# Power_Supply.net
KiCad netlist of a schematic drawn in Altium Designer
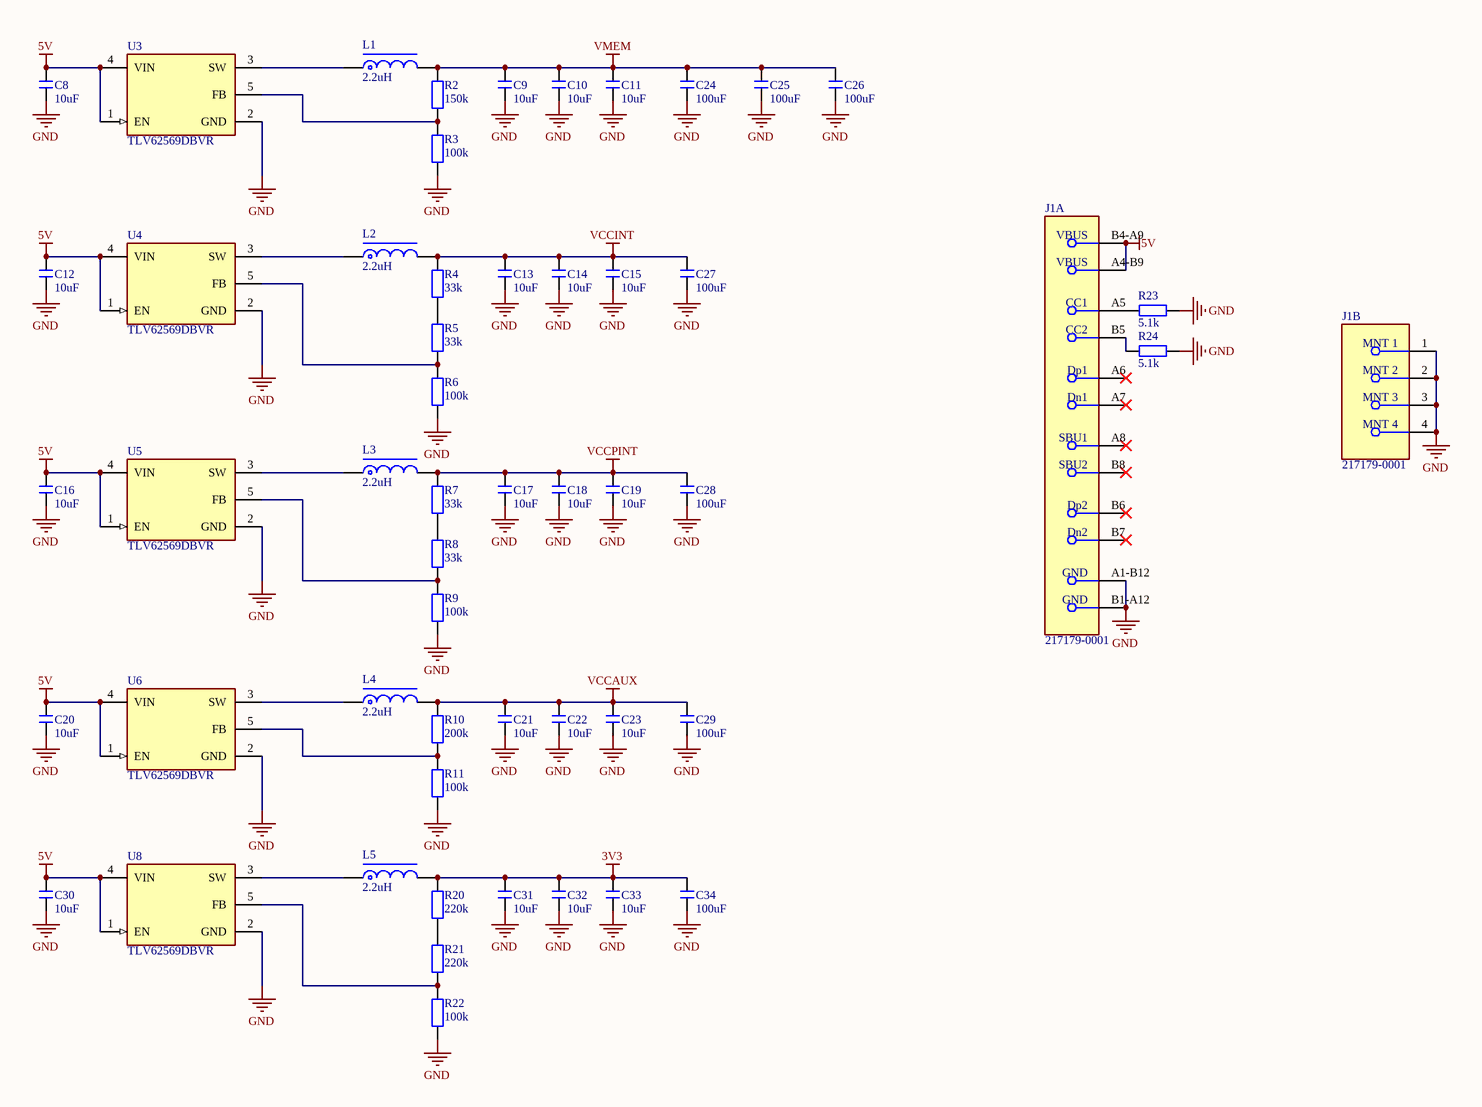
[diagram p0: Power_Supply.SchDoc]

(export (version "E")
  (design (tool "Eeschema 10.0.6"))
  (components
    (comp (ref "C8") (value "10uF") (footprint "C0603") (libsource (lib "Passive") (part "C")))
    (comp (ref "C9") (value "10uF") (footprint "C0603") (libsource (lib "Passive") (part "C")))
    (comp (ref "C10") (value "10uF") (footprint "C0603") (libsource (lib "Passive") (part "C")))
    (comp (ref "C11") (value "10uF") (footprint "C0603") (libsource (lib "Passive") (part "C")))
    (comp (ref "C12") (value "10uF") (footprint "C0603") (libsource (lib "Passive") (part "C")))
    (comp (ref "C13") (value "10uF") (footprint "C0603") (libsource (lib "Passive") (part "C")))
    (comp (ref "C14") (value "10uF") (footprint "C0603") (libsource (lib "Passive") (part "C")))
    (comp (ref "C15") (value "10uF") (footprint "C0603") (libsource (lib "Passive") (part "C")))
    (comp (ref "C16") (value "10uF") (footprint "C0603") (libsource (lib "Passive") (part "C")))
    (comp (ref "C17") (value "10uF") (footprint "C0603") (libsource (lib "Passive") (part "C")))
    (comp (ref "C18") (value "10uF") (footprint "C0603") (libsource (lib "Passive") (part "C")))
    (comp (ref "C19") (value "10uF") (footprint "C0603") (libsource (lib "Passive") (part "C")))
    (comp (ref "C20") (value "10uF") (footprint "C0603") (libsource (lib "Passive") (part "C")))
    (comp (ref "C21") (value "10uF") (footprint "C0603") (libsource (lib "Passive") (part "C")))
    (comp (ref "C22") (value "10uF") (footprint "C0603") (libsource (lib "Passive") (part "C")))
    (comp (ref "C23") (value "10uF") (footprint "C0603") (libsource (lib "Passive") (part "C")))
    (comp (ref "C24") (value "100uF") (footprint "C1206") (libsource (lib "Passive") (part "C")))
    (comp (ref "C25") (value "100uF") (footprint "C1206") (libsource (lib "Passive") (part "C")))
    (comp (ref "C26") (value "100uF") (footprint "C1206") (libsource (lib "Passive") (part "C")))
    (comp (ref "C27") (value "100uF") (footprint "C1206") (libsource (lib "Passive") (part "C")))
    (comp (ref "C28") (value "100uF") (footprint "C1206") (libsource (lib "Passive") (part "C")))
    (comp (ref "C29") (value "100uF") (footprint "C1206") (libsource (lib "Passive") (part "C")))
    (comp (ref "C30") (value "10uF") (footprint "C0603") (libsource (lib "Passive") (part "C")))
    (comp (ref "C31") (value "10uF") (footprint "C0603") (libsource (lib "Passive") (part "C")))
    (comp (ref "C32") (value "10uF") (footprint "C0603") (libsource (lib "Passive") (part "C")))
    (comp (ref "C33") (value "10uF") (footprint "C0603") (libsource (lib "Passive") (part "C")))
    (comp (ref "C34") (value "100uF") (footprint "C1206") (libsource (lib "Passive") (part "C")))
    (comp (ref "J1")
      (value "217179-0001")
      (footprint "FP-217179-0001-MFG")
      (description "CONN RCP USB2.0 TYP C 24P SMD RA")
      (libsource (lib "Altium Content Vault") (part "5f86746d156db037abd23105bb3dbc5"))
    )
    (comp (ref "L1") (value "2.2uH") (footprint "CD31") (libsource (lib "Passive") (part "L-CD")))
    (comp (ref "L2") (value "2.2uH") (footprint "CD31") (libsource (lib "Passive") (part "L-CD")))
    (comp (ref "L3") (value "2.2uH") (footprint "CD31") (libsource (lib "Passive") (part "L-CD")))
    (comp (ref "L4") (value "2.2uH") (footprint "CD31") (libsource (lib "Passive") (part "L-CD")))
    (comp (ref "L5") (value "2.2uH") (footprint "CD31") (libsource (lib "Passive") (part "L-CD")))
    (comp (ref "R2") (value "150k") (footprint "R0603") (libsource (lib "Passive") (part "R")))
    (comp (ref "R3") (value "100k") (footprint "R0603") (libsource (lib "Passive") (part "R")))
    (comp (ref "R4") (value "33k") (footprint "R0402") (libsource (lib "Passive") (part "R")))
    (comp (ref "R5") (value "33k") (footprint "R0402") (libsource (lib "Passive") (part "R")))
    (comp (ref "R6") (value "100k") (footprint "R0603") (libsource (lib "Passive") (part "R")))
    (comp (ref "R7") (value "33k") (footprint "R0402") (libsource (lib "Passive") (part "R")))
    (comp (ref "R8") (value "33k") (footprint "R0402") (libsource (lib "Passive") (part "R")))
    (comp (ref "R9") (value "100k") (footprint "R0603") (libsource (lib "Passive") (part "R")))
    (comp (ref "R10") (value "200k") (footprint "R0603") (libsource (lib "Passive") (part "R")))
    (comp (ref "R11") (value "100k") (footprint "R0603") (libsource (lib "Passive") (part "R")))
    (comp (ref "R20") (value "220k") (footprint "R0402") (libsource (lib "Passive") (part "R")))
    (comp (ref "R21") (value "220k") (footprint "R0402") (libsource (lib "Passive") (part "R")))
    (comp (ref "R22") (value "100k") (footprint "R0603") (libsource (lib "Passive") (part "R")))
    (comp (ref "R23") (value "5.1k") (footprint "R0402") (libsource (lib "Passive") (part "R")))
    (comp (ref "R24") (value "5.1k") (footprint "R0402") (libsource (lib "Passive") (part "R")))
    (comp (ref "U3")
      (value "TLV62569DBVR")
      (footprint "FP-DBV0005A-MFG")
      (description "IC REG BUCK ADJ 2A SOT23-5")
      (libsource (lib "Altium Content Vault") (part "f8671745ee5fb9a493b385c735b730b"))
    )
    (comp (ref "U4")
      (value "TLV62569DBVR")
      (footprint "FP-DBV0005A-MFG")
      (description "IC REG BUCK ADJ 2A SOT23-5")
      (libsource (lib "Altium Content Vault") (part "f8671745ee5fb9a493b385c735b730b"))
    )
    (comp (ref "U5")
      (value "TLV62569DBVR")
      (footprint "FP-DBV0005A-MFG")
      (description "IC REG BUCK ADJ 2A SOT23-5")
      (libsource (lib "Altium Content Vault") (part "f8671745ee5fb9a493b385c735b730b"))
    )
    (comp (ref "U6")
      (value "TLV62569DBVR")
      (footprint "FP-DBV0005A-MFG")
      (description "IC REG BUCK ADJ 2A SOT23-5")
      (libsource (lib "Altium Content Vault") (part "f8671745ee5fb9a493b385c735b730b"))
    )
    (comp (ref "U8")
      (value "TLV62569DBVR")
      (footprint "FP-DBV0005A-MFG")
      (description "IC REG BUCK ADJ 2A SOT23-5")
      (libsource (lib "Altium Content Vault") (part "f8671745ee5fb9a493b385c735b730b"))
    )
  )
  (nets
    (net (code "1") (name "3V3") (class "Default")
      (node (ref "C31") (pin "1") (pinfunction "1_1") (pintype "passive"))
      (node (ref "C32") (pin "1") (pinfunction "1_1") (pintype "passive"))
      (node (ref "C33") (pin "1") (pinfunction "1_1") (pintype "passive"))
      (node (ref "C34") (pin "1") (pinfunction "1_1") (pintype "passive"))
      (node (ref "L5") (pin "2") (pinfunction "2_2") (pintype "passive"))
      (node (ref "R20") (pin "2") (pinfunction "2_2") (pintype "passive"))
    )
    (net (code "2") (name "5V") (class "Default")
      (node (ref "C12") (pin "1") (pinfunction "1_1") (pintype "passive"))
      (node (ref "C16") (pin "1") (pinfunction "1_1") (pintype "passive"))
      (node (ref "C20") (pin "1") (pinfunction "1_1") (pintype "passive"))
      (node (ref "C30") (pin "1") (pinfunction "1_1") (pintype "passive"))
      (node (ref "C8") (pin "1") (pinfunction "1_1") (pintype "passive"))
      (node (ref "J1") (pin "A4-B9") (pinfunction "VBUS_A4-B9") (pintype "power_in"))
      (node (ref "J1") (pin "B4-A9") (pinfunction "VBUS_B4-A9") (pintype "power_in"))
      (node (ref "U3") (pin "1") (pinfunction "EN_1") (pintype "input"))
      (node (ref "U3") (pin "4") (pinfunction "VIN_4") (pintype "power_in"))
      (node (ref "U4") (pin "1") (pinfunction "EN_1") (pintype "input"))
      (node (ref "U4") (pin "4") (pinfunction "VIN_4") (pintype "power_in"))
      (node (ref "U5") (pin "1") (pinfunction "EN_1") (pintype "input"))
      (node (ref "U5") (pin "4") (pinfunction "VIN_4") (pintype "power_in"))
      (node (ref "U6") (pin "1") (pinfunction "EN_1") (pintype "input"))
      (node (ref "U6") (pin "4") (pinfunction "VIN_4") (pintype "power_in"))
      (node (ref "U8") (pin "1") (pinfunction "EN_1") (pintype "input"))
      (node (ref "U8") (pin "4") (pinfunction "VIN_4") (pintype "power_in"))
    )
    (net (code "3") (name "GND") (class "Default")
      (node (ref "C10") (pin "2") (pinfunction "2_2") (pintype "passive"))
      (node (ref "C11") (pin "2") (pinfunction "2_2") (pintype "passive"))
      (node (ref "C12") (pin "2") (pinfunction "2_2") (pintype "passive"))
      (node (ref "C13") (pin "2") (pinfunction "2_2") (pintype "passive"))
      (node (ref "C14") (pin "2") (pinfunction "2_2") (pintype "passive"))
      (node (ref "C15") (pin "2") (pinfunction "2_2") (pintype "passive"))
      (node (ref "C16") (pin "2") (pinfunction "2_2") (pintype "passive"))
      (node (ref "C17") (pin "2") (pinfunction "2_2") (pintype "passive"))
      (node (ref "C18") (pin "2") (pinfunction "2_2") (pintype "passive"))
      (node (ref "C19") (pin "2") (pinfunction "2_2") (pintype "passive"))
      (node (ref "C20") (pin "2") (pinfunction "2_2") (pintype "passive"))
      (node (ref "C21") (pin "2") (pinfunction "2_2") (pintype "passive"))
      (node (ref "C22") (pin "2") (pinfunction "2_2") (pintype "passive"))
      (node (ref "C23") (pin "2") (pinfunction "2_2") (pintype "passive"))
      (node (ref "C24") (pin "2") (pinfunction "2_2") (pintype "passive"))
      (node (ref "C25") (pin "2") (pinfunction "2_2") (pintype "passive"))
      (node (ref "C26") (pin "2") (pinfunction "2_2") (pintype "passive"))
      (node (ref "C27") (pin "2") (pinfunction "2_2") (pintype "passive"))
      (node (ref "C28") (pin "2") (pinfunction "2_2") (pintype "passive"))
      (node (ref "C29") (pin "2") (pinfunction "2_2") (pintype "passive"))
      (node (ref "C30") (pin "2") (pinfunction "2_2") (pintype "passive"))
      (node (ref "C31") (pin "2") (pinfunction "2_2") (pintype "passive"))
      (node (ref "C32") (pin "2") (pinfunction "2_2") (pintype "passive"))
      (node (ref "C33") (pin "2") (pinfunction "2_2") (pintype "passive"))
      (node (ref "C34") (pin "2") (pinfunction "2_2") (pintype "passive"))
      (node (ref "C8") (pin "2") (pinfunction "2_2") (pintype "passive"))
      (node (ref "C9") (pin "2") (pinfunction "2_2") (pintype "passive"))
      (node (ref "J1") (pin "1") (pinfunction "MNT_1_1") (pintype "passive"))
      (node (ref "J1") (pin "2") (pinfunction "MNT_2_2") (pintype "passive"))
      (node (ref "J1") (pin "3") (pinfunction "MNT_3_3") (pintype "passive"))
      (node (ref "J1") (pin "4") (pinfunction "MNT_4_4") (pintype "passive"))
      (node (ref "J1") (pin "A1-B12") (pinfunction "GND_A1-B12") (pintype "power_in"))
      (node (ref "J1") (pin "B1-A12") (pinfunction "GND_B1-A12") (pintype "power_in"))
      (node (ref "R11") (pin "1") (pinfunction "1_1") (pintype "passive"))
      (node (ref "R22") (pin "1") (pinfunction "1_1") (pintype "passive"))
      (node (ref "R23") (pin "1") (pinfunction "1_1") (pintype "passive"))
      (node (ref "R24") (pin "1") (pinfunction "1_1") (pintype "passive"))
      (node (ref "R3") (pin "1") (pinfunction "1_1") (pintype "passive"))
      (node (ref "R6") (pin "1") (pinfunction "1_1") (pintype "passive"))
      (node (ref "R9") (pin "1") (pinfunction "1_1") (pintype "passive"))
      (node (ref "U3") (pin "2") (pinfunction "GND_2") (pintype "power_in"))
      (node (ref "U4") (pin "2") (pinfunction "GND_2") (pintype "power_in"))
      (node (ref "U5") (pin "2") (pinfunction "GND_2") (pintype "power_in"))
      (node (ref "U6") (pin "2") (pinfunction "GND_2") (pintype "power_in"))
      (node (ref "U8") (pin "2") (pinfunction "GND_2") (pintype "power_in"))
    )
    (net (code "4") (name "Net-(J1A-CC1)") (class "Default")
      (node (ref "J1") (pin "A5") (pinfunction "CC1_A5") (pintype "passive"))
      (node (ref "R23") (pin "2") (pinfunction "2_2") (pintype "passive"))
    )
    (net (code "5") (name "Net-(J1A-CC2)") (class "Default")
      (node (ref "J1") (pin "B5") (pinfunction "CC2_B5") (pintype "passive"))
      (node (ref "R24") (pin "2") (pinfunction "2_2") (pintype "passive"))
    )
    (net (code "6") (name "Net-(R4-Pad1)") (class "Default")
      (node (ref "R4") (pin "1") (pinfunction "1_1") (pintype "passive"))
      (node (ref "R5") (pin "2") (pinfunction "2_2") (pintype "passive"))
    )
    (net (code "7") (name "Net-(R7-Pad1)") (class "Default")
      (node (ref "R7") (pin "1") (pinfunction "1_1") (pintype "passive"))
      (node (ref "R8") (pin "2") (pinfunction "2_2") (pintype "passive"))
    )
    (net (code "8") (name "Net-(R20-Pad1)") (class "Default")
      (node (ref "R20") (pin "1") (pinfunction "1_1") (pintype "passive"))
      (node (ref "R21") (pin "2") (pinfunction "2_2") (pintype "passive"))
    )
    (net (code "9") (name "Net-(U3-FB)") (class "Default")
      (node (ref "R2") (pin "1") (pinfunction "1_1") (pintype "passive"))
      (node (ref "R3") (pin "2") (pinfunction "2_2") (pintype "passive"))
      (node (ref "U3") (pin "5") (pinfunction "FB_5") (pintype "passive"))
    )
    (net (code "10") (name "Net-(U3-SW)") (class "Default")
      (node (ref "L1") (pin "1") (pinfunction "1_1") (pintype "passive"))
      (node (ref "U3") (pin "3") (pinfunction "SW_3") (pintype "power_in"))
    )
    (net (code "11") (name "Net-(U4-FB)") (class "Default")
      (node (ref "R5") (pin "1") (pinfunction "1_1") (pintype "passive"))
      (node (ref "R6") (pin "2") (pinfunction "2_2") (pintype "passive"))
      (node (ref "U4") (pin "5") (pinfunction "FB_5") (pintype "passive"))
    )
    (net (code "12") (name "Net-(U4-SW)") (class "Default")
      (node (ref "L2") (pin "1") (pinfunction "1_1") (pintype "passive"))
      (node (ref "U4") (pin "3") (pinfunction "SW_3") (pintype "power_in"))
    )
    (net (code "13") (name "Net-(U5-FB)") (class "Default")
      (node (ref "R8") (pin "1") (pinfunction "1_1") (pintype "passive"))
      (node (ref "R9") (pin "2") (pinfunction "2_2") (pintype "passive"))
      (node (ref "U5") (pin "5") (pinfunction "FB_5") (pintype "passive"))
    )
    (net (code "14") (name "Net-(U5-SW)") (class "Default")
      (node (ref "L3") (pin "1") (pinfunction "1_1") (pintype "passive"))
      (node (ref "U5") (pin "3") (pinfunction "SW_3") (pintype "power_in"))
    )
    (net (code "15") (name "Net-(U6-FB)") (class "Default")
      (node (ref "R10") (pin "1") (pinfunction "1_1") (pintype "passive"))
      (node (ref "R11") (pin "2") (pinfunction "2_2") (pintype "passive"))
      (node (ref "U6") (pin "5") (pinfunction "FB_5") (pintype "passive"))
    )
    (net (code "16") (name "Net-(U6-SW)") (class "Default")
      (node (ref "L4") (pin "1") (pinfunction "1_1") (pintype "passive"))
      (node (ref "U6") (pin "3") (pinfunction "SW_3") (pintype "power_in"))
    )
    (net (code "17") (name "Net-(U8-FB)") (class "Default")
      (node (ref "R21") (pin "1") (pinfunction "1_1") (pintype "passive"))
      (node (ref "R22") (pin "2") (pinfunction "2_2") (pintype "passive"))
      (node (ref "U8") (pin "5") (pinfunction "FB_5") (pintype "passive"))
    )
    (net (code "18") (name "Net-(U8-SW)") (class "Default")
      (node (ref "L5") (pin "1") (pinfunction "1_1") (pintype "passive"))
      (node (ref "U8") (pin "3") (pinfunction "SW_3") (pintype "power_in"))
    )
    (net (code "19") (name "VCCAUX") (class "Default")
      (node (ref "C21") (pin "1") (pinfunction "1_1") (pintype "passive"))
      (node (ref "C22") (pin "1") (pinfunction "1_1") (pintype "passive"))
      (node (ref "C23") (pin "1") (pinfunction "1_1") (pintype "passive"))
      (node (ref "C29") (pin "1") (pinfunction "1_1") (pintype "passive"))
      (node (ref "L4") (pin "2") (pinfunction "2_2") (pintype "passive"))
      (node (ref "R10") (pin "2") (pinfunction "2_2") (pintype "passive"))
    )
    (net (code "20") (name "VCCINT") (class "Default")
      (node (ref "C13") (pin "1") (pinfunction "1_1") (pintype "passive"))
      (node (ref "C14") (pin "1") (pinfunction "1_1") (pintype "passive"))
      (node (ref "C15") (pin "1") (pinfunction "1_1") (pintype "passive"))
      (node (ref "C27") (pin "1") (pinfunction "1_1") (pintype "passive"))
      (node (ref "L2") (pin "2") (pinfunction "2_2") (pintype "passive"))
      (node (ref "R4") (pin "2") (pinfunction "2_2") (pintype "passive"))
    )
    (net (code "21") (name "VCCPINT") (class "Default")
      (node (ref "C17") (pin "1") (pinfunction "1_1") (pintype "passive"))
      (node (ref "C18") (pin "1") (pinfunction "1_1") (pintype "passive"))
      (node (ref "C19") (pin "1") (pinfunction "1_1") (pintype "passive"))
      (node (ref "C28") (pin "1") (pinfunction "1_1") (pintype "passive"))
      (node (ref "L3") (pin "2") (pinfunction "2_2") (pintype "passive"))
      (node (ref "R7") (pin "2") (pinfunction "2_2") (pintype "passive"))
    )
    (net (code "22") (name "VMEM") (class "Default")
      (node (ref "C10") (pin "1") (pinfunction "1_1") (pintype "passive"))
      (node (ref "C11") (pin "1") (pinfunction "1_1") (pintype "passive"))
      (node (ref "C24") (pin "1") (pinfunction "1_1") (pintype "passive"))
      (node (ref "C25") (pin "1") (pinfunction "1_1") (pintype "passive"))
      (node (ref "C26") (pin "1") (pinfunction "1_1") (pintype "passive"))
      (node (ref "C9") (pin "1") (pinfunction "1_1") (pintype "passive"))
      (node (ref "L1") (pin "2") (pinfunction "2_2") (pintype "passive"))
      (node (ref "R2") (pin "2") (pinfunction "2_2") (pintype "passive"))
    )
    (net (code "23") (name "unconnected-(J1A-Dn1-PadA7)") (class "Default")
      (node (ref "J1") (pin "A7") (pinfunction "Dn1_A7") (pintype "passive+no_connect"))
    )
    (net (code "24") (name "unconnected-(J1A-Dn2-PadB7)") (class "Default")
      (node (ref "J1") (pin "B7") (pinfunction "Dn2_B7") (pintype "passive+no_connect"))
    )
    (net (code "25") (name "unconnected-(J1A-Dp1-PadA6)") (class "Default")
      (node (ref "J1") (pin "A6") (pinfunction "Dp1_A6") (pintype "passive+no_connect"))
    )
    (net (code "26") (name "unconnected-(J1A-Dp2-PadB6)") (class "Default")
      (node (ref "J1") (pin "B6") (pinfunction "Dp2_B6") (pintype "passive+no_connect"))
    )
    (net (code "27") (name "unconnected-(J1A-SBU1-PadA8)") (class "Default")
      (node (ref "J1") (pin "A8") (pinfunction "SBU1_A8") (pintype "passive+no_connect"))
    )
    (net (code "28") (name "unconnected-(J1A-SBU2-PadB8)") (class "Default")
      (node (ref "J1") (pin "B8") (pinfunction "SBU2_B8") (pintype "passive+no_connect"))
    )
  )
)
